# switch.net
KiCad netlist of a schematic drawn in Altium Designer
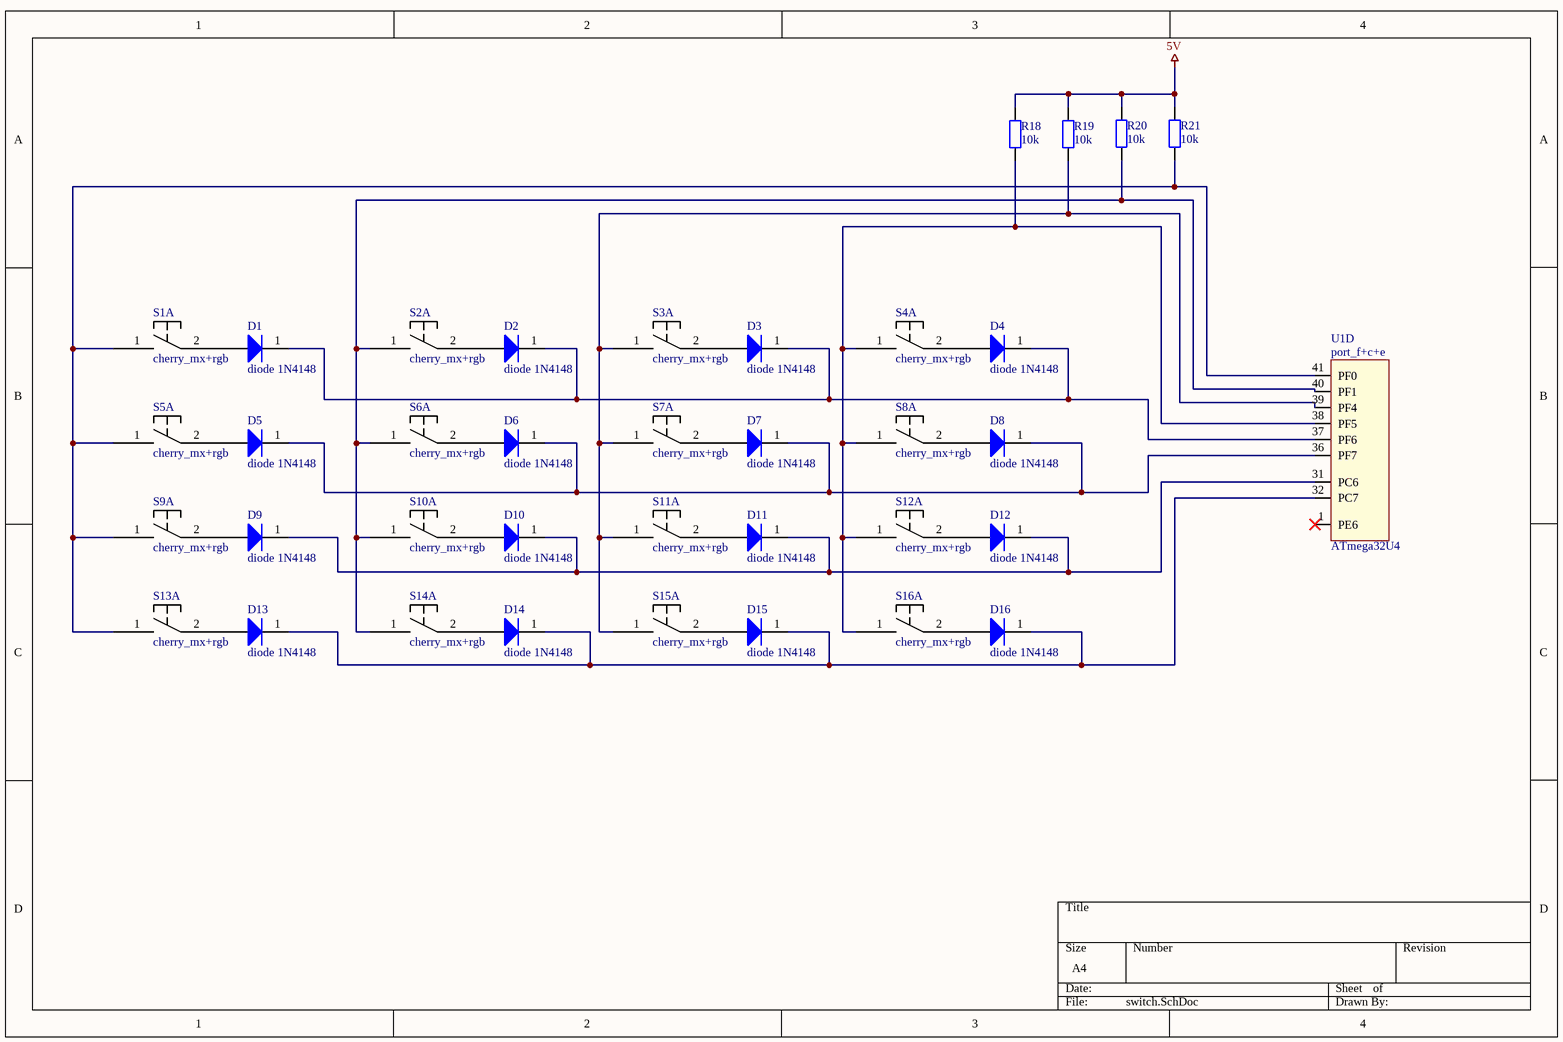
[diagram p0: switch.SchDoc]

(export (version "E")
  (design (tool "Eeschema 10.0.6"))
  (components
    (comp (ref "D1")
      (value "diode 1N4148")
      (footprint "SOD-323_S130X260")
      (libsource (lib "generic_components") (part "diode 1N4148"))
    )
    (comp (ref "D2")
      (value "diode 1N4148")
      (footprint "SOD-323_S130X260")
      (libsource (lib "generic_components") (part "diode 1N4148"))
    )
    (comp (ref "D3")
      (value "diode 1N4148")
      (footprint "SOD-323_S130X260")
      (libsource (lib "generic_components") (part "diode 1N4148"))
    )
    (comp (ref "D4")
      (value "diode 1N4148")
      (footprint "SOD-323_S130X260")
      (libsource (lib "generic_components") (part "diode 1N4148"))
    )
    (comp (ref "D5")
      (value "diode 1N4148")
      (footprint "SOD-323_S130X260")
      (libsource (lib "generic_components") (part "diode 1N4148"))
    )
    (comp (ref "D6")
      (value "diode 1N4148")
      (footprint "SOD-323_S130X260")
      (libsource (lib "generic_components") (part "diode 1N4148"))
    )
    (comp (ref "D7")
      (value "diode 1N4148")
      (footprint "SOD-323_S130X260")
      (libsource (lib "generic_components") (part "diode 1N4148"))
    )
    (comp (ref "D8")
      (value "diode 1N4148")
      (footprint "SOD-323_S130X260")
      (libsource (lib "generic_components") (part "diode 1N4148"))
    )
    (comp (ref "D9")
      (value "diode 1N4148")
      (footprint "SOD-323_S130X260")
      (libsource (lib "generic_components") (part "diode 1N4148"))
    )
    (comp (ref "D10")
      (value "diode 1N4148")
      (footprint "SOD-323_S130X260")
      (libsource (lib "generic_components") (part "diode 1N4148"))
    )
    (comp (ref "D11")
      (value "diode 1N4148")
      (footprint "SOD-323_S130X260")
      (libsource (lib "generic_components") (part "diode 1N4148"))
    )
    (comp (ref "D12")
      (value "diode 1N4148")
      (footprint "SOD-323_S130X260")
      (libsource (lib "generic_components") (part "diode 1N4148"))
    )
    (comp (ref "D13")
      (value "diode 1N4148")
      (footprint "SOD-323_S130X260")
      (libsource (lib "generic_components") (part "diode 1N4148"))
    )
    (comp (ref "D14")
      (value "diode 1N4148")
      (footprint "SOD-323_S130X260")
      (libsource (lib "generic_components") (part "diode 1N4148"))
    )
    (comp (ref "D15")
      (value "diode 1N4148")
      (footprint "SOD-323_S130X260")
      (libsource (lib "generic_components") (part "diode 1N4148"))
    )
    (comp (ref "D16")
      (value "diode 1N4148")
      (footprint "SOD-323_S130X260")
      (libsource (lib "generic_components") (part "diode 1N4148"))
    )
    (comp (ref "R18")
      (value "10k")
      (footprint "0805")
      (libsource (lib "generic_components") (part "res0805"))
    )
    (comp (ref "R19")
      (value "10k")
      (footprint "0805")
      (libsource (lib "generic_components") (part "res0805"))
    )
    (comp (ref "R20")
      (value "10k")
      (footprint "0805")
      (libsource (lib "generic_components") (part "res0805"))
    )
    (comp (ref "R21")
      (value "10k")
      (footprint "0805")
      (libsource (lib "generic_components") (part "res0805"))
    )
    (comp (ref "S1")
      (value "cherry_mx+rgb")
      (footprint "kailh_socket_mx+led")
      (libsource (lib "mx") (part "cherry_mx+rgb"))
    )
    (comp (ref "S2")
      (value "cherry_mx+rgb")
      (footprint "kailh_socket_mx+led")
      (libsource (lib "mx") (part "cherry_mx+rgb"))
    )
    (comp (ref "S3")
      (value "cherry_mx+rgb")
      (footprint "kailh_socket_mx+led")
      (libsource (lib "mx") (part "cherry_mx+rgb"))
    )
    (comp (ref "S4")
      (value "cherry_mx+rgb")
      (footprint "kailh_socket_mx+led")
      (libsource (lib "mx") (part "cherry_mx+rgb"))
    )
    (comp (ref "S5")
      (value "cherry_mx+rgb")
      (footprint "kailh_socket_mx+led")
      (libsource (lib "mx") (part "cherry_mx+rgb"))
    )
    (comp (ref "S6")
      (value "cherry_mx+rgb")
      (footprint "kailh_socket_mx+led")
      (libsource (lib "mx") (part "cherry_mx+rgb"))
    )
    (comp (ref "S7")
      (value "cherry_mx+rgb")
      (footprint "kailh_socket_mx+led")
      (libsource (lib "mx") (part "cherry_mx+rgb"))
    )
    (comp (ref "S8")
      (value "cherry_mx+rgb")
      (footprint "kailh_socket_mx+led")
      (libsource (lib "mx") (part "cherry_mx+rgb"))
    )
    (comp (ref "S9")
      (value "cherry_mx+rgb")
      (footprint "kailh_socket_mx+led")
      (libsource (lib "mx") (part "cherry_mx+rgb"))
    )
    (comp (ref "S10")
      (value "cherry_mx+rgb")
      (footprint "kailh_socket_mx+led")
      (libsource (lib "mx") (part "cherry_mx+rgb"))
    )
    (comp (ref "S11")
      (value "cherry_mx+rgb")
      (footprint "kailh_socket_mx+led")
      (libsource (lib "mx") (part "cherry_mx+rgb"))
    )
    (comp (ref "S12")
      (value "cherry_mx+rgb")
      (footprint "kailh_socket_mx+led")
      (libsource (lib "mx") (part "cherry_mx+rgb"))
    )
    (comp (ref "S13")
      (value "cherry_mx+rgb")
      (footprint "kailh_socket_mx+led")
      (libsource (lib "mx") (part "cherry_mx+rgb"))
    )
    (comp (ref "S14")
      (value "cherry_mx+rgb")
      (footprint "kailh_socket_mx+led")
      (libsource (lib "mx") (part "cherry_mx+rgb"))
    )
    (comp (ref "S15")
      (value "cherry_mx+rgb")
      (footprint "kailh_socket_mx+led")
      (libsource (lib "mx") (part "cherry_mx+rgb"))
    )
    (comp (ref "S16")
      (value "cherry_mx+rgb")
      (footprint "kailh_socket_mx+led")
      (libsource (lib "mx") (part "cherry_mx+rgb"))
    )
    (comp (ref "U1")
      (value "ATmega32U4")
      (footprint "QFN44P05P7X7")
      (libsource (lib "atmel") (part "ATmega32U4"))
    )
  )
  (nets
    (net (code "1") (name "5V") (class "Default")
      (node (ref "R18") (pin "2") (pinfunction "2_2") (pintype "passive"))
      (node (ref "R19") (pin "2") (pinfunction "2_2") (pintype "passive"))
      (node (ref "R20") (pin "2") (pinfunction "2_2") (pintype "passive"))
      (node (ref "R21") (pin "2") (pinfunction "2_2") (pintype "passive"))
    )
    (net (code "2") (name "Net-(D1-A)") (class "Default")
      (node (ref "D1") (pin "2") (pinfunction "A_2") (pintype "passive"))
      (node (ref "S1") (pin "2") (pintype "power_in"))
    )
    (net (code "3") (name "Net-(D1-K)") (class "Default")
      (node (ref "D1") (pin "1") (pinfunction "K_1") (pintype "passive"))
      (node (ref "D2") (pin "1") (pinfunction "K_1") (pintype "passive"))
      (node (ref "D3") (pin "1") (pinfunction "K_1") (pintype "passive"))
      (node (ref "D4") (pin "1") (pinfunction "K_1") (pintype "passive"))
      (node (ref "U1") (pin "37") (pinfunction "PF6_37") (pintype "bidirectional"))
    )
    (net (code "4") (name "Net-(D2-A)") (class "Default")
      (node (ref "D2") (pin "2") (pinfunction "A_2") (pintype "passive"))
      (node (ref "S2") (pin "2") (pintype "power_in"))
    )
    (net (code "5") (name "Net-(D3-A)") (class "Default")
      (node (ref "D3") (pin "2") (pinfunction "A_2") (pintype "passive"))
      (node (ref "S3") (pin "2") (pintype "power_in"))
    )
    (net (code "6") (name "Net-(D4-A)") (class "Default")
      (node (ref "D4") (pin "2") (pinfunction "A_2") (pintype "passive"))
      (node (ref "S4") (pin "2") (pintype "power_in"))
    )
    (net (code "7") (name "Net-(D5-A)") (class "Default")
      (node (ref "D5") (pin "2") (pinfunction "A_2") (pintype "passive"))
      (node (ref "S5") (pin "2") (pintype "power_in"))
    )
    (net (code "8") (name "Net-(D5-K)") (class "Default")
      (node (ref "D5") (pin "1") (pinfunction "K_1") (pintype "passive"))
      (node (ref "D6") (pin "1") (pinfunction "K_1") (pintype "passive"))
      (node (ref "D7") (pin "1") (pinfunction "K_1") (pintype "passive"))
      (node (ref "D8") (pin "1") (pinfunction "K_1") (pintype "passive"))
      (node (ref "U1") (pin "36") (pinfunction "PF7_36") (pintype "bidirectional"))
    )
    (net (code "9") (name "Net-(D6-A)") (class "Default")
      (node (ref "D6") (pin "2") (pinfunction "A_2") (pintype "passive"))
      (node (ref "S6") (pin "2") (pintype "power_in"))
    )
    (net (code "10") (name "Net-(D7-A)") (class "Default")
      (node (ref "D7") (pin "2") (pinfunction "A_2") (pintype "passive"))
      (node (ref "S7") (pin "2") (pintype "power_in"))
    )
    (net (code "11") (name "Net-(D8-A)") (class "Default")
      (node (ref "D8") (pin "2") (pinfunction "A_2") (pintype "passive"))
      (node (ref "S8") (pin "2") (pintype "power_in"))
    )
    (net (code "12") (name "Net-(D9-A)") (class "Default")
      (node (ref "D9") (pin "2") (pinfunction "A_2") (pintype "passive"))
      (node (ref "S9") (pin "2") (pintype "power_in"))
    )
    (net (code "13") (name "Net-(D10-A)") (class "Default")
      (node (ref "D10") (pin "2") (pinfunction "A_2") (pintype "passive"))
      (node (ref "S10") (pin "2") (pintype "power_in"))
    )
    (net (code "14") (name "Net-(D10-K)") (class "Default")
      (node (ref "D10") (pin "1") (pinfunction "K_1") (pintype "passive"))
      (node (ref "D11") (pin "1") (pinfunction "K_1") (pintype "passive"))
      (node (ref "D12") (pin "1") (pinfunction "K_1") (pintype "passive"))
      (node (ref "D9") (pin "1") (pinfunction "K_1") (pintype "passive"))
      (node (ref "U1") (pin "31") (pinfunction "PC6_31") (pintype "bidirectional"))
    )
    (net (code "15") (name "Net-(D11-A)") (class "Default")
      (node (ref "D11") (pin "2") (pinfunction "A_2") (pintype "passive"))
      (node (ref "S11") (pin "2") (pintype "power_in"))
    )
    (net (code "16") (name "Net-(D12-A)") (class "Default")
      (node (ref "D12") (pin "2") (pinfunction "A_2") (pintype "passive"))
      (node (ref "S12") (pin "2") (pintype "power_in"))
    )
    (net (code "17") (name "Net-(D13-A)") (class "Default")
      (node (ref "D13") (pin "2") (pinfunction "A_2") (pintype "passive"))
      (node (ref "S13") (pin "2") (pintype "power_in"))
    )
    (net (code "18") (name "Net-(D13-K)") (class "Default")
      (node (ref "D13") (pin "1") (pinfunction "K_1") (pintype "passive"))
      (node (ref "D14") (pin "1") (pinfunction "K_1") (pintype "passive"))
      (node (ref "D15") (pin "1") (pinfunction "K_1") (pintype "passive"))
      (node (ref "D16") (pin "1") (pinfunction "K_1") (pintype "passive"))
      (node (ref "U1") (pin "32") (pinfunction "PC7_32") (pintype "bidirectional"))
    )
    (net (code "19") (name "Net-(D14-A)") (class "Default")
      (node (ref "D14") (pin "2") (pinfunction "A_2") (pintype "passive"))
      (node (ref "S14") (pin "2") (pintype "power_in"))
    )
    (net (code "20") (name "Net-(D15-A)") (class "Default")
      (node (ref "D15") (pin "2") (pinfunction "A_2") (pintype "passive"))
      (node (ref "S15") (pin "2") (pintype "power_in"))
    )
    (net (code "21") (name "Net-(D16-A)") (class "Default")
      (node (ref "D16") (pin "2") (pinfunction "A_2") (pintype "passive"))
      (node (ref "S16") (pin "2") (pintype "power_in"))
    )
    (net (code "22") (name "Net-(U1D-PF0)") (class "Default")
      (node (ref "R21") (pin "1") (pintype "passive"))
      (node (ref "S1") (pin "1") (pintype "power_in"))
      (node (ref "S13") (pin "1") (pintype "power_in"))
      (node (ref "S5") (pin "1") (pintype "power_in"))
      (node (ref "S9") (pin "1") (pintype "power_in"))
      (node (ref "U1") (pin "41") (pinfunction "PF0_41") (pintype "bidirectional"))
    )
    (net (code "23") (name "Net-(U1D-PF1)") (class "Default")
      (node (ref "R20") (pin "1") (pintype "passive"))
      (node (ref "S10") (pin "1") (pintype "power_in"))
      (node (ref "S14") (pin "1") (pintype "power_in"))
      (node (ref "S2") (pin "1") (pintype "power_in"))
      (node (ref "S6") (pin "1") (pintype "power_in"))
      (node (ref "U1") (pin "40") (pinfunction "PF1_40") (pintype "bidirectional"))
    )
    (net (code "24") (name "Net-(U1D-PF4)") (class "Default")
      (node (ref "R19") (pin "1") (pintype "passive"))
      (node (ref "S11") (pin "1") (pintype "power_in"))
      (node (ref "S15") (pin "1") (pintype "power_in"))
      (node (ref "S3") (pin "1") (pintype "power_in"))
      (node (ref "S7") (pin "1") (pintype "power_in"))
      (node (ref "U1") (pin "39") (pinfunction "PF4_39") (pintype "bidirectional"))
    )
    (net (code "25") (name "Net-(U1D-PF5)") (class "Default")
      (node (ref "R18") (pin "1") (pintype "passive"))
      (node (ref "S12") (pin "1") (pintype "power_in"))
      (node (ref "S16") (pin "1") (pintype "power_in"))
      (node (ref "S4") (pin "1") (pintype "power_in"))
      (node (ref "S8") (pin "1") (pintype "power_in"))
      (node (ref "U1") (pin "38") (pinfunction "PF5_38") (pintype "bidirectional"))
    )
    (net (code "26") (name "unconnected-(U1D-PE6-Pad1)") (class "Default")
      (node (ref "U1") (pin "1") (pinfunction "PE6_1") (pintype "bidirectional+no_connect"))
    )
  )
)
